# gsm_module.net
KiCad netlist of a schematic drawn in EAGLE
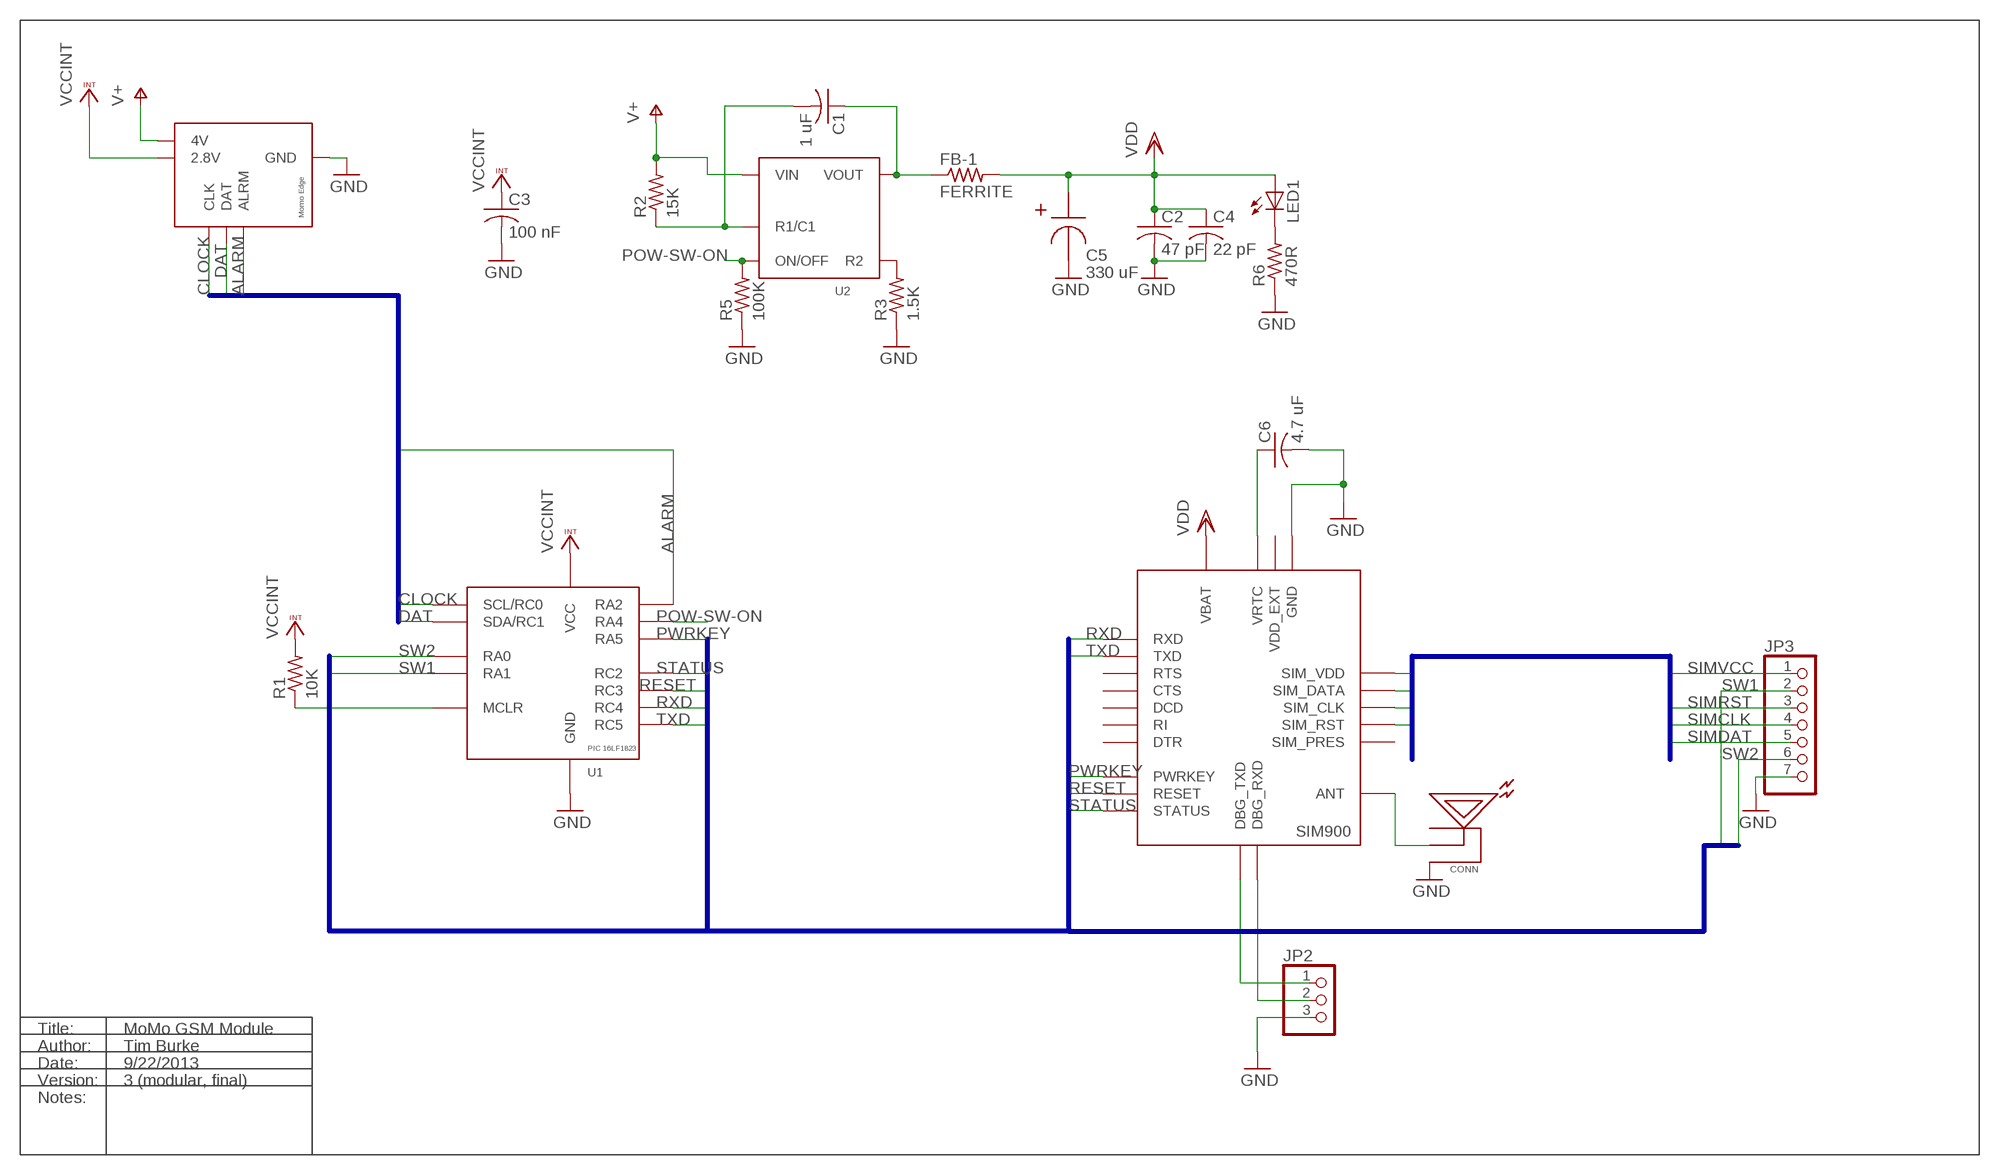
[diagram p0: schematic, sheet 1]

(export (version "E")
  (design (tool "Eeschema 10.0.6"))
  (components
    (comp (ref "C1")
      (value "1 uF")
      (footprint "eagle-import:C0402K")
      (libsource (lib "eagle-import") (part "C-USC0402K"))
    )
    (comp (ref "C2")
      (value "47 pF")
      (footprint "eagle-import:C0402K")
      (libsource (lib "eagle-import") (part "C-USC0402K"))
    )
    (comp (ref "C3")
      (value "100 nF")
      (footprint "eagle-import:C0402")
      (libsource (lib "eagle-import") (part "C-USC0402"))
    )
    (comp (ref "C4")
      (value "22 pF")
      (footprint "eagle-import:C0402K")
      (libsource (lib "eagle-import") (part "C-USC0402K"))
    )
    (comp (ref "C5")
      (value "330 uF")
      (footprint "eagle-import:2917")
      (libsource (lib "eagle-import") (part "TANTALUM_CAP"))
    )
    (comp (ref "C6")
      (value "4.7 uF")
      (footprint "eagle-import:C0805")
      (libsource (lib "eagle-import") (part "C-USC0805"))
    )
    (comp (ref "CONN")
      (value "RFANTENNA")
      (footprint "eagle-import:RFJACK")
      (libsource (lib "eagle-import") (part "RFANTENNA"))
    )
    (comp (ref "FB-1")
      (value "FERRITE")
      (footprint "eagle-import:R0805")
      (libsource (lib "eagle-import") (part "R-US_R0805"))
    )
    (comp (ref "JP1")
      (value "MOMO-EDGE-6M")
      (footprint "eagle-import:MOMO-EDGE-6M")
      (libsource (lib "eagle-import") (part "MOMO-EDGE-6M"))
    )
    (comp (ref "JP2")
      (value "PINHD-1X3")
      (footprint "eagle-import:1X03")
      (libsource (lib "eagle-import") (part "PINHD-1X3"))
    )
    (comp (ref "JP3")
      (value "PINHD-1X7")
      (footprint "eagle-import:1X07")
      (libsource (lib "eagle-import") (part "PINHD-1X7"))
    )
    (comp (ref "LED1")
      (value "LEDCHIPLED_0603")
      (footprint "eagle-import:CHIPLED_0603")
      (libsource (lib "eagle-import") (part "LEDCHIPLED_0603"))
    )
    (comp (ref "R1")
      (value "10K")
      (footprint "eagle-import:R0603")
      (libsource (lib "eagle-import") (part "R-US_R0603"))
    )
    (comp (ref "R2")
      (value "15K")
      (footprint "eagle-import:R0603")
      (libsource (lib "eagle-import") (part "R-US_R0603"))
    )
    (comp (ref "R3")
      (value "1.5K")
      (footprint "eagle-import:R0603")
      (libsource (lib "eagle-import") (part "R-US_R0603"))
    )
    (comp (ref "R5")
      (value "100K")
      (footprint "eagle-import:R0603")
      (libsource (lib "eagle-import") (part "R-US_R0603"))
    )
    (comp (ref "R6")
      (value "470R")
      (footprint "eagle-import:R0603")
      (libsource (lib "eagle-import") (part "R-US_R0603"))
    )
    (comp (ref "U1")
      (value "PIC16LF1823")
      (footprint "eagle-import:SO14")
      (libsource (lib "eagle-import") (part "PIC16LF1823"))
    )
    (comp (ref "U2")
      (value "TI-HIGHSIDE-PFET")
      (footprint "eagle-import:SOT23-6L")
      (libsource (lib "eagle-import") (part "TI-HIGHSIDE-PFET"))
    )
    (comp (ref "U3")
      (value "SIM900")
      (footprint "eagle-import:SIM900")
      (libsource (lib "eagle-import") (part "SIM900"))
    )
  )
  (nets
    (net (code "1") (name "/ALARM") (class "Default")
      (node (ref "JP1") (pin "ALARM") (pinfunction "ALRM_ALARM") (pintype "bidirectional"))
      (node (ref "U1") (pin "11") (pinfunction "RA2_11") (pintype "bidirectional"))
    )
    (net (code "2") (name "/CLOCK") (class "Default")
      (node (ref "JP1") (pin "CLK") (pinfunction "CLK_CLK") (pintype "bidirectional"))
      (node (ref "U1") (pin "10") (pinfunction "SCL/RC0_10") (pintype "bidirectional"))
    )
    (net (code "3") (name "/DAT") (class "Default")
      (node (ref "JP1") (pin "DAT") (pinfunction "DAT_DAT") (pintype "bidirectional"))
      (node (ref "U1") (pin "9") (pinfunction "SDA/RC1_9") (pintype "bidirectional"))
    )
    (net (code "4") (name "/POW-SW-ON") (class "Default")
      (node (ref "R5") (pin "2") (pinfunction "2_2") (pintype "passive"))
      (node (ref "U1") (pin "3") (pinfunction "RA4_3") (pintype "bidirectional"))
      (node (ref "U2") (pin "5") (pinfunction "ON/OFF_5") (pintype "bidirectional"))
    )
    (net (code "5") (name "/PWRKEY") (class "Default")
      (node (ref "U1") (pin "2") (pinfunction "RA5_2") (pintype "bidirectional"))
      (node (ref "U3") (pin "1") (pinfunction "PWRKEY_1") (pintype "bidirectional"))
    )
    (net (code "6") (name "/RESET") (class "Default")
      (node (ref "U1") (pin "7") (pinfunction "RC3_7") (pintype "bidirectional"))
      (node (ref "U3") (pin "16") (pinfunction "RESET_16") (pintype "bidirectional"))
    )
    (net (code "7") (name "/RXD") (class "Default")
      (node (ref "U1") (pin "6") (pinfunction "RC4_6") (pintype "bidirectional"))
      (node (ref "U3") (pin "10") (pinfunction "RXD_10") (pintype "bidirectional"))
    )
    (net (code "8") (name "/SIMCLK") (class "Default")
      (node (ref "JP3") (pin "4") (pinfunction "4_4") (pintype "passive"))
      (node (ref "U3") (pin "32") (pinfunction "SIM_CLK_32") (pintype "bidirectional"))
    )
    (net (code "9") (name "/SIMDAT") (class "Default")
      (node (ref "JP3") (pin "5") (pinfunction "5_5") (pintype "passive"))
      (node (ref "U3") (pin "31") (pinfunction "SIM_DATA_31") (pintype "bidirectional"))
    )
    (net (code "10") (name "/SIMRST") (class "Default")
      (node (ref "JP3") (pin "3") (pinfunction "3_3") (pintype "passive"))
      (node (ref "U3") (pin "33") (pinfunction "SIM_RST_33") (pintype "bidirectional"))
    )
    (net (code "11") (name "/SIMVCC") (class "Default")
      (node (ref "JP3") (pin "1") (pinfunction "1_1") (pintype "passive"))
      (node (ref "U3") (pin "30") (pinfunction "SIM_VDD_30") (pintype "bidirectional"))
    )
    (net (code "12") (name "/STATUS") (class "Default")
      (node (ref "U1") (pin "8") (pinfunction "RC2_8") (pintype "bidirectional"))
      (node (ref "U3") (pin "66") (pinfunction "STATUS_66") (pintype "bidirectional"))
    )
    (net (code "13") (name "/SW1") (class "Default")
      (node (ref "JP3") (pin "2") (pinfunction "2_2") (pintype "passive"))
      (node (ref "U1") (pin "12") (pinfunction "RA1_12") (pintype "bidirectional"))
    )
    (net (code "14") (name "/SW2") (class "Default")
      (node (ref "JP3") (pin "6") (pinfunction "6_6") (pintype "passive"))
      (node (ref "U1") (pin "13") (pinfunction "RA0_13") (pintype "bidirectional"))
    )
    (net (code "15") (name "/TXD") (class "Default")
      (node (ref "U1") (pin "5") (pinfunction "RC5_5") (pintype "bidirectional"))
      (node (ref "U3") (pin "9") (pinfunction "TXD_9") (pintype "bidirectional"))
    )
    (net (code "16") (name "/VDD_EXT") (class "Default")
      (node (ref "U3") (pin "15") (pinfunction "VDD_EXT_15") (pintype "power_in"))
    )
    (net (code "17") (name "GND") (class "Default")
      (node (ref "C2") (pin "2") (pinfunction "2_2") (pintype "passive"))
      (node (ref "C3") (pin "2") (pinfunction "2_2") (pintype "passive"))
      (node (ref "C4") (pin "2") (pinfunction "2_2") (pintype "passive"))
      (node (ref "C5") (pin "-") (pinfunction "-_-") (pintype "bidirectional"))
      (node (ref "C6") (pin "2") (pinfunction "2_2") (pintype "passive"))
      (node (ref "CONN") (pin "UNUSED1") (pinfunction "SHIELD_UNUSED1") (pintype "power_in"))
      (node (ref "CONN") (pin "UNUSED2") (pinfunction "SHIELD_UNUSED2") (pintype "power_in"))
      (node (ref "JP1") (pin "GND") (pinfunction "GND_GND") (pintype "power_in"))
      (node (ref "JP2") (pin "3") (pinfunction "3_3") (pintype "passive"))
      (node (ref "JP3") (pin "7") (pinfunction "7_7") (pintype "passive"))
      (node (ref "R3") (pin "1") (pinfunction "1_1") (pintype "passive"))
      (node (ref "R5") (pin "1") (pinfunction "1_1") (pintype "passive"))
      (node (ref "R6") (pin "1") (pinfunction "1_1") (pintype "passive"))
      (node (ref "U1") (pin "14") (pinfunction "GND_14") (pintype "power_in"))
      (node (ref "U3") (pin "17") (pinfunction "GND_17") (pintype "power_in"))
      (node (ref "U3") (pin "18") (pinfunction "GND_18") (pintype "power_in"))
      (node (ref "U3") (pin "29") (pinfunction "GND_29") (pintype "power_in"))
      (node (ref "U3") (pin "39") (pinfunction "GND_39") (pintype "power_in"))
      (node (ref "U3") (pin "45") (pinfunction "GND_45") (pintype "power_in"))
      (node (ref "U3") (pin "46") (pinfunction "GND_46") (pintype "power_in"))
      (node (ref "U3") (pin "53") (pinfunction "GND_53") (pintype "power_in"))
      (node (ref "U3") (pin "54") (pinfunction "GND_54") (pintype "power_in"))
      (node (ref "U3") (pin "58") (pinfunction "GND_58") (pintype "power_in"))
      (node (ref "U3") (pin "59") (pinfunction "GND_59") (pintype "power_in"))
      (node (ref "U3") (pin "61") (pinfunction "GND_61") (pintype "power_in"))
      (node (ref "U3") (pin "62") (pinfunction "GND_62") (pintype "power_in"))
      (node (ref "U3") (pin "63") (pinfunction "GND_63") (pintype "power_in"))
      (node (ref "U3") (pin "64") (pinfunction "GND_64") (pintype "power_in"))
      (node (ref "U3") (pin "65") (pinfunction "GND_65") (pintype "power_in"))
    )
    (net (code "18") (name "Net-(C1-Pad1)") (class "Default")
      (node (ref "C1") (pin "1") (pinfunction "1_1") (pintype "passive"))
      (node (ref "FB-1") (pin "1") (pinfunction "1_1") (pintype "passive"))
      (node (ref "U2") (pin "2") (pinfunction "VOUT_2") (pintype "power_in"))
      (node (ref "U2") (pin "3") (pinfunction "VOUT_3") (pintype "power_in"))
    )
    (net (code "19") (name "Net-(CONN-PIN)") (class "Default")
      (node (ref "CONN") (pin "ANTENNA") (pinfunction "PIN_ANTENNA") (pintype "bidirectional"))
      (node (ref "U3") (pin "60") (pinfunction "ANT_60") (pintype "bidirectional"))
    )
    (net (code "20") (name "Net-(LED1-PadC)") (class "Default")
      (node (ref "LED1") (pin "C") (pinfunction "C_C") (pintype "passive"))
      (node (ref "R6") (pin "2") (pinfunction "2_2") (pintype "passive"))
    )
    (net (code "21") (name "Net-(U1-MCLR)") (class "Default")
      (node (ref "R1") (pin "1") (pinfunction "1_1") (pintype "passive"))
      (node (ref "U1") (pin "4") (pinfunction "MCLR_4") (pintype "bidirectional"))
    )
    (net (code "22") (name "Net-(U2-R1{slash}C1)") (class "Default")
      (node (ref "C1") (pin "2") (pinfunction "2_2") (pintype "passive"))
      (node (ref "R2") (pin "1") (pinfunction "1_1") (pintype "passive"))
      (node (ref "U2") (pin "6") (pinfunction "R1/C1_6") (pintype "power_in"))
    )
    (net (code "23") (name "Net-(U2-R2)") (class "Default")
      (node (ref "R3") (pin "2") (pinfunction "2_2") (pintype "passive"))
      (node (ref "U2") (pin "1") (pinfunction "R2_1") (pintype "power_in"))
    )
    (net (code "24") (name "Net-(U3-DBG_RXD)") (class "Default")
      (node (ref "JP2") (pin "2") (pinfunction "2_2") (pintype "passive"))
      (node (ref "U3") (pin "28") (pinfunction "DBG_RXD_28") (pintype "bidirectional"))
    )
    (net (code "25") (name "Net-(U3-DBG_TXD)") (class "Default")
      (node (ref "JP2") (pin "1") (pinfunction "1_1") (pintype "passive"))
      (node (ref "U3") (pin "27") (pinfunction "DBG_TXD_27") (pintype "bidirectional"))
    )
    (net (code "26") (name "Net-(U3-VRTC)") (class "Default")
      (node (ref "C6") (pin "1") (pinfunction "1_1") (pintype "passive"))
      (node (ref "U3") (pin "26") (pinfunction "VRTC_26") (pintype "power_in"))
    )
    (net (code "27") (name "V+") (class "Default")
      (node (ref "JP1") (pin "4V") (pinfunction "4V_4V") (pintype "power_in"))
      (node (ref "R2") (pin "2") (pinfunction "2_2") (pintype "passive"))
      (node (ref "U2") (pin "4") (pinfunction "VIN_4") (pintype "power_in"))
    )
    (net (code "28") (name "VCCINT") (class "Default")
      (node (ref "C3") (pin "1") (pinfunction "1_1") (pintype "passive"))
      (node (ref "JP1") (pin "V28") (pinfunction "2.8V_V28") (pintype "power_in"))
      (node (ref "R1") (pin "2") (pinfunction "2_2") (pintype "passive"))
      (node (ref "U1") (pin "1") (pinfunction "VCC_1") (pintype "power_in"))
    )
    (net (code "29") (name "VDD") (class "Default")
      (node (ref "C2") (pin "1") (pinfunction "1_1") (pintype "passive"))
      (node (ref "C4") (pin "1") (pinfunction "1_1") (pintype "passive"))
      (node (ref "C5") (pin "+") (pinfunction "+_+") (pintype "bidirectional"))
      (node (ref "FB-1") (pin "2") (pinfunction "2_2") (pintype "passive"))
      (node (ref "LED1") (pin "A") (pinfunction "A_A") (pintype "passive"))
      (node (ref "U3") (pin "55") (pinfunction "VBAT_55") (pintype "power_in"))
      (node (ref "U3") (pin "56") (pinfunction "VBAT_56") (pintype "power_in"))
      (node (ref "U3") (pin "57") (pinfunction "VBAT_57") (pintype "power_in"))
    )
    (net (code "30") (name "unconnected-(U3-CTS-Pad7)") (class "Default")
      (node (ref "U3") (pin "7") (pinfunction "CTS_7") (pintype "bidirectional"))
    )
    (net (code "31") (name "unconnected-(U3-DCD-Pad5)") (class "Default")
      (node (ref "U3") (pin "5") (pinfunction "DCD_5") (pintype "bidirectional"))
    )
    (net (code "32") (name "unconnected-(U3-DTR-Pad3)") (class "Default")
      (node (ref "U3") (pin "3") (pinfunction "DTR_3") (pintype "bidirectional"))
    )
    (net (code "33") (name "unconnected-(U3-RI-Pad4)") (class "Default")
      (node (ref "U3") (pin "4") (pinfunction "RI_4") (pintype "bidirectional"))
    )
    (net (code "34") (name "unconnected-(U3-RTS-Pad8)") (class "Default")
      (node (ref "U3") (pin "8") (pinfunction "RTS_8") (pintype "bidirectional"))
    )
    (net (code "35") (name "unconnected-(U3-SIM_PRES-Pad34)") (class "Default")
      (node (ref "U3") (pin "34") (pinfunction "SIM_PRES_34") (pintype "bidirectional"))
    )
  )
)
